# DeskClock1.net
KiCad netlist of a schematic drawn in Altium Designer
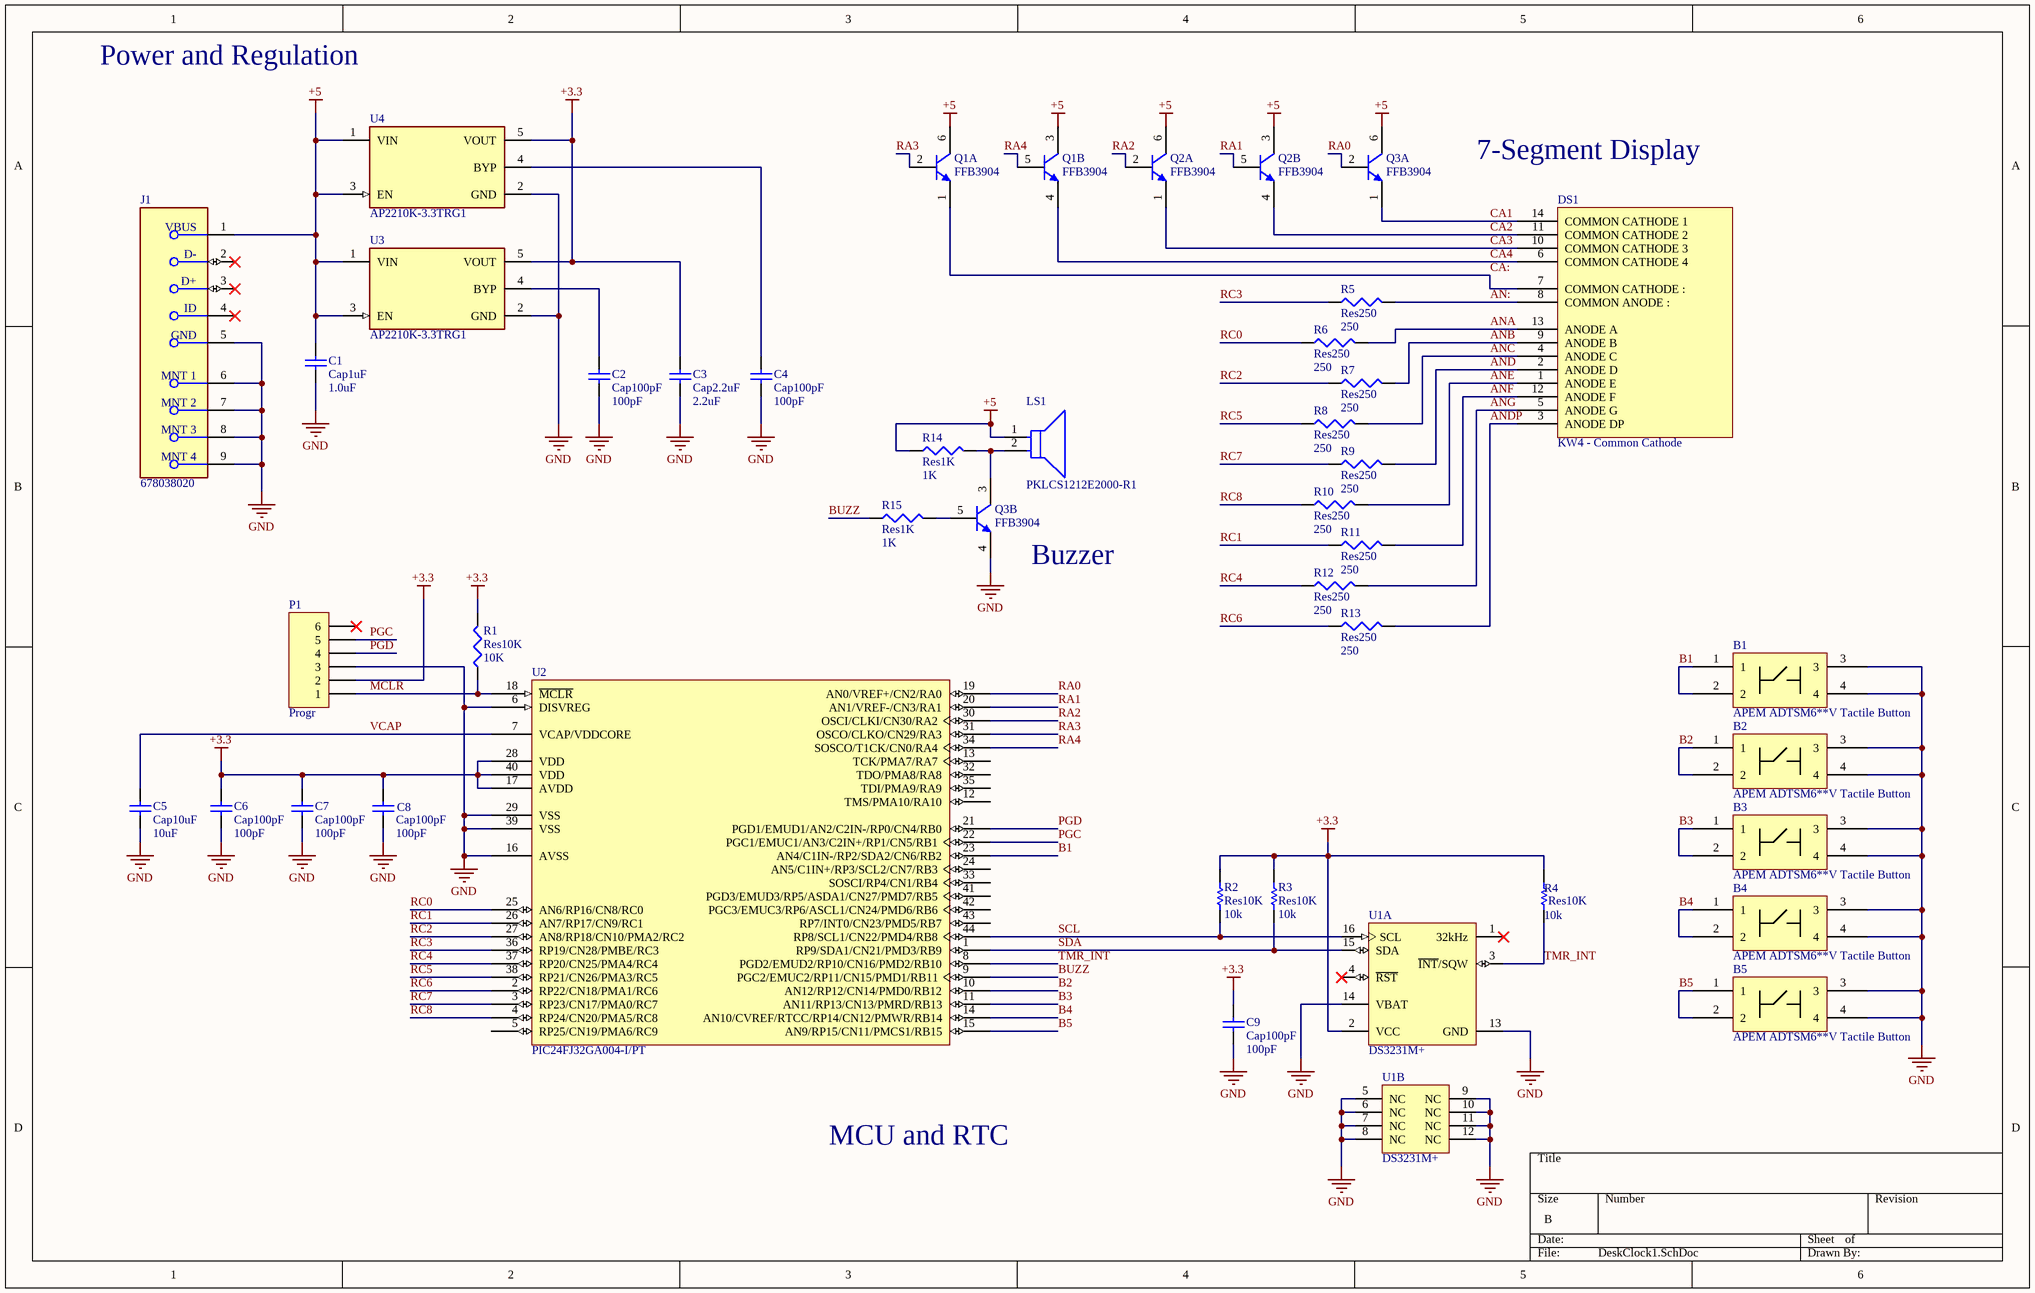
[diagram p0: DeskClock1.SchDoc]

(export (version "E")
  (design (tool "Eeschema 10.0.6"))
  (components
    (comp (ref "B1")
      (value "APEM ADTSM6**V Tactile Button")
      (footprint "ADTSM6**V")
      (description "ADTSM6**V")
      (libsource (lib "Button") (part "Button"))
    )
    (comp (ref "B2")
      (value "APEM ADTSM6**V Tactile Button")
      (footprint "ADTSM6**V")
      (description "ADTSM6**V")
      (libsource (lib "Button") (part "Button"))
    )
    (comp (ref "B3")
      (value "APEM ADTSM6**V Tactile Button")
      (footprint "ADTSM6**V")
      (description "ADTSM6**V")
      (libsource (lib "Button") (part "Button"))
    )
    (comp (ref "B4")
      (value "APEM ADTSM6**V Tactile Button")
      (footprint "ADTSM6**V")
      (description "ADTSM6**V")
      (libsource (lib "Button") (part "Button"))
    )
    (comp (ref "B5")
      (value "APEM ADTSM6**V Tactile Button")
      (footprint "ADTSM6**V")
      (description "ADTSM6**V")
      (libsource (lib "Button") (part "Button"))
    )
    (comp (ref "C1")
      (value "Cap1uF")
      (footprint "C1206")
      (description "Capacitor (Semiconductor SIM Model)")
      (fields (field (name "ALTIUM_VALUE") "1.0uF") (field (name "PUBLISHER") "Altium Limited"))
      (libsource (lib "Miscellaneous Devices") (part "Cap Semi"))
    )
    (comp (ref "C2")
      (value "Cap100pF")
      (footprint "C1206")
      (description "Capacitor (Semiconductor SIM Model)")
      (fields (field (name "ALTIUM_VALUE") "100pF") (field (name "PUBLISHER") "Altium Limited"))
      (libsource (lib "Miscellaneous Devices") (part "Cap Semi"))
    )
    (comp (ref "C3")
      (value "Cap2.2uF")
      (footprint "C1206")
      (description "Capacitor (Semiconductor SIM Model)")
      (fields (field (name "ALTIUM_VALUE") "2.2uF") (field (name "PUBLISHER") "Altium Limited"))
      (libsource (lib "Miscellaneous Devices") (part "Cap Semi"))
    )
    (comp (ref "C4")
      (value "Cap100pF")
      (footprint "C1206")
      (description "Capacitor (Semiconductor SIM Model)")
      (fields (field (name "ALTIUM_VALUE") "100pF") (field (name "PUBLISHER") "Altium Limited"))
      (libsource (lib "Miscellaneous Devices") (part "Cap Semi"))
    )
    (comp (ref "C5")
      (value "Cap10uF")
      (footprint "C1206")
      (description "Capacitor (Semiconductor SIM Model)")
      (fields (field (name "ALTIUM_VALUE") "10uF") (field (name "PUBLISHER") "Altium Limited"))
      (libsource (lib "Miscellaneous Devices") (part "Cap Semi"))
    )
    (comp (ref "C6")
      (value "Cap100pF")
      (footprint "C1206")
      (description "Capacitor (Semiconductor SIM Model)")
      (fields (field (name "ALTIUM_VALUE") "100pF") (field (name "PUBLISHER") "Altium Limited"))
      (libsource (lib "Miscellaneous Devices") (part "Cap Semi"))
    )
    (comp (ref "C7")
      (value "Cap100pF")
      (footprint "C1206")
      (description "Capacitor (Semiconductor SIM Model)")
      (fields (field (name "ALTIUM_VALUE") "100pF") (field (name "PUBLISHER") "Altium Limited"))
      (libsource (lib "Miscellaneous Devices") (part "Cap Semi"))
    )
    (comp (ref "C8")
      (value "Cap100pF")
      (footprint "C1206")
      (description "Capacitor (Semiconductor SIM Model)")
      (fields (field (name "ALTIUM_VALUE") "100pF") (field (name "PUBLISHER") "Altium Limited"))
      (libsource (lib "Miscellaneous Devices") (part "Cap Semi"))
    )
    (comp (ref "C9")
      (value "Cap100pF")
      (footprint "C1206")
      (description "Capacitor (Semiconductor SIM Model)")
      (fields (field (name "ALTIUM_VALUE") "100pF") (field (name "PUBLISHER") "Altium Limited"))
      (libsource (lib "Miscellaneous Devices") (part "Cap Semi"))
    )
    (comp (ref "DS1")
      (value "KW4 - Common Cathode")
      (footprint "KW4-56")
      (description "Lucky Light 4-digit 7 segment clock display")
      (libsource (lib "7SegDisplay") (part "KW4 - Common Cathode"))
    )
    (comp (ref "J1")
      (value "678038020")
      (footprint "FP-678038020-MFG")
      (description "CONN RCPT USB2.0 MINI AB SMD R/A")
      (fields
        (field (name "OCTOPART") "https://octopart.com/67803-8020-molex-7136109")
        (field (name "MANUFACTURER") "Molex")
      )
      (libsource (lib "Altium Content Vault") (part "4e344dc6d88d84069f7b4209354b9f9"))
    )
    (comp (ref "LS1")
      (value "PKLCS1212E2000-R1")
      (footprint "FP-PKLCS1212E2000-R1-MFG")
      (description "AUDIO PIEZO TRANSDUCER 12.5V SMD")
      (fields
        (field (name "MANUFACTURER") "Murata")
        (field (name "OCTOPART") "https://octopart.com/pklcs1212e2000-r1-murata-7123179")
      )
      (libsource (lib "Altium Content Vault") (part "5f581d31613f872430949aa526fd155"))
    )
    (comp (ref "P1")
      (value "Progr")
      (footprint "HDR1X6")
      (description "Header, 6-Pin")
      (fields (field (name "PUBLISHER") "Altium Limited"))
      (libsource (lib "Miscellaneous Connectors") (part "Header 6"))
    )
    (comp (ref "Q1")
      (value "FFB3904")
      (footprint "FAIR-SC70-6_V")
      (fields (field (name "MANUFACTURER") "FairchildSemiconductor"))
      (libsource (lib "Altium Content Vault") (part "BJT-NPN-EBC-EBC-6_A"))
    )
    (comp (ref "Q2")
      (value "FFB3904")
      (footprint "FAIR-SC70-6_V")
      (fields (field (name "MANUFACTURER") "FairchildSemiconductor"))
      (libsource (lib "Altium Content Vault") (part "BJT-NPN-EBC-EBC-6_A"))
    )
    (comp (ref "Q3")
      (value "FFB3904")
      (footprint "FAIR-SC70-6_V")
      (fields (field (name "MANUFACTURER") "FairchildSemiconductor"))
      (libsource (lib "Altium Content Vault") (part "BJT-NPN-EBC-EBC-6_A"))
    )
    (comp (ref "R1")
      (value "Res10K")
      (footprint "C1206")
      (description "Resistor")
      (fields (field (name "ALTIUM_VALUE") "10K") (field (name "PUBLISHER") "Altium Limited"))
      (libsource (lib "Miscellaneous Devices") (part "Res3"))
    )
    (comp (ref "R2")
      (value "Res10K")
      (footprint "C1206")
      (description "Resistor")
      (fields (field (name "ALTIUM_VALUE") "10k") (field (name "PUBLISHER") "Altium Limited"))
      (libsource (lib "Miscellaneous Devices") (part "Res1"))
    )
    (comp (ref "R3")
      (value "Res10K")
      (footprint "C1206")
      (description "Resistor")
      (fields (field (name "ALTIUM_VALUE") "10k") (field (name "PUBLISHER") "Altium Limited"))
      (libsource (lib "Miscellaneous Devices") (part "Res1"))
    )
    (comp (ref "R4")
      (value "Res10K")
      (footprint "C1206")
      (description "Resistor")
      (fields (field (name "ALTIUM_VALUE") "10k") (field (name "PUBLISHER") "Altium Limited"))
      (libsource (lib "Miscellaneous Devices") (part "Res1"))
    )
    (comp (ref "R5")
      (value "Res250")
      (footprint "C1206")
      (description "Resistor")
      (fields (field (name "ALTIUM_VALUE") "250") (field (name "PUBLISHER") "Altium Limited"))
      (libsource (lib "Miscellaneous Devices") (part "Res3"))
    )
    (comp (ref "R6")
      (value "Res250")
      (footprint "C1206")
      (description "Resistor")
      (fields (field (name "ALTIUM_VALUE") "250") (field (name "PUBLISHER") "Altium Limited"))
      (libsource (lib "Miscellaneous Devices") (part "Res3"))
    )
    (comp (ref "R7")
      (value "Res250")
      (footprint "C1206")
      (description "Resistor")
      (fields (field (name "ALTIUM_VALUE") "250") (field (name "PUBLISHER") "Altium Limited"))
      (libsource (lib "Miscellaneous Devices") (part "Res3"))
    )
    (comp (ref "R8")
      (value "Res250")
      (footprint "C1206")
      (description "Resistor")
      (fields (field (name "ALTIUM_VALUE") "250") (field (name "PUBLISHER") "Altium Limited"))
      (libsource (lib "Miscellaneous Devices") (part "Res3"))
    )
    (comp (ref "R9")
      (value "Res250")
      (footprint "C1206")
      (description "Resistor")
      (fields (field (name "ALTIUM_VALUE") "250") (field (name "PUBLISHER") "Altium Limited"))
      (libsource (lib "Miscellaneous Devices") (part "Res3"))
    )
    (comp (ref "R10")
      (value "Res250")
      (footprint "C1206")
      (description "Resistor")
      (fields (field (name "ALTIUM_VALUE") "250") (field (name "PUBLISHER") "Altium Limited"))
      (libsource (lib "Miscellaneous Devices") (part "Res3"))
    )
    (comp (ref "R11")
      (value "Res250")
      (footprint "C1206")
      (description "Resistor")
      (fields (field (name "ALTIUM_VALUE") "250") (field (name "PUBLISHER") "Altium Limited"))
      (libsource (lib "Miscellaneous Devices") (part "Res3"))
    )
    (comp (ref "R12")
      (value "Res250")
      (footprint "C1206")
      (description "Resistor")
      (fields (field (name "ALTIUM_VALUE") "250") (field (name "PUBLISHER") "Altium Limited"))
      (libsource (lib "Miscellaneous Devices") (part "Res3"))
    )
    (comp (ref "R13")
      (value "Res250")
      (footprint "C1206")
      (description "Resistor")
      (fields (field (name "ALTIUM_VALUE") "250") (field (name "PUBLISHER") "Altium Limited"))
      (libsource (lib "Miscellaneous Devices") (part "Res3"))
    )
    (comp (ref "R14")
      (value "Res1K")
      (footprint "C1206")
      (description "Resistor")
      (fields (field (name "ALTIUM_VALUE") "1K") (field (name "PUBLISHER") "Altium Limited"))
      (libsource (lib "Miscellaneous Devices") (part "Res3"))
    )
    (comp (ref "R15")
      (value "Res1K")
      (footprint "C1206")
      (description "Resistor")
      (fields (field (name "ALTIUM_VALUE") "1K") (field (name "PUBLISHER") "Altium Limited"))
      (libsource (lib "Miscellaneous Devices") (part "Res3"))
    )
    (comp (ref "U1")
      (value "DS3231M+")
      (footprint "W16MK+1_M")
      (description "+/-5ppm, MEMS based Real-Time Clock, I2C Interface, 16-Pin SO, -40 to 85 degC, Pb-Free")
      (libsource (lib "Altium Content Vault") (part "PR-RTC-DS3231M-IL16"))
    )
    (comp (ref "U2")
      (value "PIC24FJ32GA004-I/PT")
      (footprint "TQFP-PT44_L")
      (libsource (lib "Altium Content Vault") (part "MC-16B-16GA004-TQFP44"))
    )
    (comp (ref "U3")
      (value "AP2210K-3.3TRG1")
      (footprint "FP-SOT25-MFG")
      (description "IC REG LINEAR 3.3V 300MA SOT23-5")
      (fields
        (field (name "MANUFACTURER") "Diodes")
        (field (name "OCTOPART") "https://octopart.com/ap2210k-3.3trg1-diodes+inc.-30954630")
      )
      (libsource (lib "Altium Content Vault") (part "c51eb117839baecd597f0ee1e447120"))
    )
    (comp (ref "U4")
      (value "AP2210K-3.3TRG1")
      (footprint "FP-SOT25-MFG")
      (description "IC REG LINEAR 3.3V 300MA SOT23-5")
      (fields
        (field (name "MANUFACTURER") "Diodes")
        (field (name "OCTOPART") "https://octopart.com/ap2210k-3.3trg1-diodes+inc.-30954630")
      )
      (libsource (lib "Altium Content Vault") (part "c51eb117839baecd597f0ee1e447120"))
    )
  )
  (nets
    (net (code "1") (name "+3.3") (class "Default")
      (node (ref "C3") (pin "2") (pinfunction "2_2") (pintype "passive"))
      (node (ref "C6") (pin "2") (pinfunction "2_2") (pintype "passive"))
      (node (ref "C7") (pin "2") (pinfunction "2_2") (pintype "passive"))
      (node (ref "C8") (pin "2") (pinfunction "2_2") (pintype "passive"))
      (node (ref "C9") (pin "2") (pinfunction "2_2") (pintype "passive"))
      (node (ref "P1") (pin "2") (pinfunction "2_2") (pintype "passive"))
      (node (ref "R1") (pin "2") (pinfunction "2_2") (pintype "passive"))
      (node (ref "R2") (pin "2") (pinfunction "2_2") (pintype "passive"))
      (node (ref "R3") (pin "2") (pinfunction "2_2") (pintype "passive"))
      (node (ref "R4") (pin "2") (pinfunction "2_2") (pintype "passive"))
      (node (ref "U1") (pin "2") (pinfunction "VCC_2") (pintype "power_in"))
      (node (ref "U2") (pin "17") (pinfunction "AVDD_17") (pintype "power_in"))
      (node (ref "U2") (pin "28") (pinfunction "VDD_28") (pintype "power_in"))
      (node (ref "U2") (pin "40") (pinfunction "VDD_40") (pintype "power_in"))
      (node (ref "U3") (pin "5") (pinfunction "VOUT_5") (pintype "power_in"))
      (node (ref "U4") (pin "5") (pinfunction "VOUT_5") (pintype "power_in"))
    )
    (net (code "2") (name "+5") (class "Default")
      (node (ref "C1") (pin "2") (pinfunction "2_2") (pintype "passive"))
      (node (ref "J1") (pin "1") (pinfunction "VBUS_1") (pintype "power_in"))
      (node (ref "LS1") (pin "1") (pinfunction "1_1") (pintype "passive"))
      (node (ref "Q1") (pin "3") (pinfunction "C2_3") (pintype "passive"))
      (node (ref "Q1") (pin "6") (pinfunction "C1_6") (pintype "passive"))
      (node (ref "Q2") (pin "3") (pinfunction "C2_3") (pintype "passive"))
      (node (ref "Q2") (pin "6") (pinfunction "C1_6") (pintype "passive"))
      (node (ref "Q3") (pin "6") (pinfunction "C1_6") (pintype "passive"))
      (node (ref "R14") (pin "1") (pinfunction "1_1") (pintype "passive"))
      (node (ref "U3") (pin "1") (pinfunction "VIN_1") (pintype "power_in"))
      (node (ref "U3") (pin "3") (pinfunction "EN_3") (pintype "input"))
      (node (ref "U4") (pin "1") (pinfunction "VIN_1") (pintype "power_in"))
      (node (ref "U4") (pin "3") (pinfunction "EN_3") (pintype "input"))
    )
    (net (code "3") (name "/AN:") (class "Default")
      (node (ref "DS1") (pin "8") (pinfunction "COMMON_ANODE_:_8") (pintype "passive"))
      (node (ref "R5") (pin "2") (pinfunction "2_2") (pintype "passive"))
    )
    (net (code "4") (name "/ANA") (class "Default")
      (node (ref "DS1") (pin "13") (pinfunction "ANODE_A_13") (pintype "passive"))
      (node (ref "R6") (pin "2") (pinfunction "2_2") (pintype "passive"))
    )
    (net (code "5") (name "/ANB") (class "Default")
      (node (ref "DS1") (pin "9") (pinfunction "ANODE_B_9") (pintype "passive"))
      (node (ref "R7") (pin "2") (pinfunction "2_2") (pintype "passive"))
    )
    (net (code "6") (name "/ANC") (class "Default")
      (node (ref "DS1") (pin "4") (pinfunction "ANODE_C_4") (pintype "passive"))
      (node (ref "R8") (pin "2") (pinfunction "2_2") (pintype "passive"))
    )
    (net (code "7") (name "/AND") (class "Default")
      (node (ref "DS1") (pin "2") (pinfunction "ANODE_D_2") (pintype "passive"))
      (node (ref "R9") (pin "2") (pinfunction "2_2") (pintype "passive"))
    )
    (net (code "8") (name "/ANDP") (class "Default")
      (node (ref "DS1") (pin "3") (pinfunction "ANODE_DP_3") (pintype "passive"))
      (node (ref "R13") (pin "2") (pinfunction "2_2") (pintype "passive"))
    )
    (net (code "9") (name "/ANE") (class "Default")
      (node (ref "DS1") (pin "1") (pinfunction "ANODE_E_1") (pintype "passive"))
      (node (ref "R10") (pin "2") (pinfunction "2_2") (pintype "passive"))
    )
    (net (code "10") (name "/ANF") (class "Default")
      (node (ref "DS1") (pin "12") (pinfunction "ANODE_F_12") (pintype "passive"))
      (node (ref "R11") (pin "2") (pinfunction "2_2") (pintype "passive"))
    )
    (net (code "11") (name "/ANG") (class "Default")
      (node (ref "DS1") (pin "5") (pinfunction "ANODE_G_5") (pintype "passive"))
      (node (ref "R12") (pin "2") (pinfunction "2_2") (pintype "passive"))
    )
    (net (code "12") (name "/B1") (class "Default")
      (node (ref "B1") (pin "1") (pinfunction "1_1") (pintype "passive"))
      (node (ref "B1") (pin "2") (pinfunction "2_2") (pintype "passive"))
      (node (ref "U2") (pin "23") (pinfunction "AN4/C1IN-/RP2/SDA2/CN6/RB2_23") (pintype "bidirectional"))
    )
    (net (code "13") (name "/B2") (class "Default")
      (node (ref "B2") (pin "1") (pinfunction "1_1") (pintype "passive"))
      (node (ref "B2") (pin "2") (pinfunction "2_2") (pintype "passive"))
      (node (ref "U2") (pin "10") (pinfunction "AN12/RP12/CN14/PMD0/RB12_10") (pintype "bidirectional"))
    )
    (net (code "14") (name "/B3") (class "Default")
      (node (ref "B3") (pin "1") (pinfunction "1_1") (pintype "passive"))
      (node (ref "B3") (pin "2") (pinfunction "2_2") (pintype "passive"))
      (node (ref "U2") (pin "11") (pinfunction "AN11/RP13/CN13/PMRD/RB13_11") (pintype "bidirectional"))
    )
    (net (code "15") (name "/B4") (class "Default")
      (node (ref "B4") (pin "1") (pinfunction "1_1") (pintype "passive"))
      (node (ref "B4") (pin "2") (pinfunction "2_2") (pintype "passive"))
      (node (ref "U2") (pin "14") (pinfunction "AN10/CVREF/RTCC/RP14/CN12/PMWR/RB14_14") (pintype "bidirectional"))
    )
    (net (code "16") (name "/B5") (class "Default")
      (node (ref "B5") (pin "1") (pinfunction "1_1") (pintype "passive"))
      (node (ref "B5") (pin "2") (pinfunction "2_2") (pintype "passive"))
      (node (ref "U2") (pin "15") (pinfunction "AN9/RP15/CN11/PMCS1/RB15_15") (pintype "bidirectional"))
    )
    (net (code "17") (name "/BUZZ") (class "Default")
      (node (ref "R15") (pin "1") (pinfunction "1_1") (pintype "passive"))
      (node (ref "U2") (pin "9") (pinfunction "PGC2/EMUC2/RP11/CN15/PMD1/RB11_9") (pintype "bidirectional"))
    )
    (net (code "18") (name "/CA1") (class "Default")
      (node (ref "DS1") (pin "14") (pinfunction "COMMON_CATHODE_1_14") (pintype "passive"))
      (node (ref "Q3") (pin "1") (pinfunction "E1_1") (pintype "passive"))
    )
    (net (code "19") (name "/CA2") (class "Default")
      (node (ref "DS1") (pin "11") (pinfunction "COMMON_CATHODE_2_11") (pintype "passive"))
      (node (ref "Q2") (pin "4") (pinfunction "E2_4") (pintype "passive"))
    )
    (net (code "20") (name "/CA3") (class "Default")
      (node (ref "DS1") (pin "10") (pinfunction "COMMON_CATHODE_3_10") (pintype "passive"))
      (node (ref "Q2") (pin "1") (pinfunction "E1_1") (pintype "passive"))
    )
    (net (code "21") (name "/CA4") (class "Default")
      (node (ref "DS1") (pin "6") (pinfunction "COMMON_CATHODE_4_6") (pintype "passive"))
      (node (ref "Q1") (pin "4") (pinfunction "E2_4") (pintype "passive"))
    )
    (net (code "22") (name "/CA:") (class "Default")
      (node (ref "DS1") (pin "7") (pinfunction "COMMON_CATHODE_:_7") (pintype "passive"))
      (node (ref "Q1") (pin "1") (pinfunction "E1_1") (pintype "passive"))
    )
    (net (code "23") (name "/MCLR") (class "Default")
      (node (ref "P1") (pin "1") (pinfunction "1_1") (pintype "passive"))
      (node (ref "R1") (pin "1") (pinfunction "1_1") (pintype "passive"))
      (node (ref "U2") (pin "18") (pinfunction "~{MCLR}_18") (pintype "input"))
    )
    (net (code "24") (name "/PGC") (class "Default")
      (node (ref "P1") (pin "5") (pinfunction "5_5") (pintype "passive"))
      (node (ref "U2") (pin "22") (pinfunction "PGC1/EMUC1/AN3/C2IN+/RP1/CN5/RB1_22") (pintype "bidirectional"))
    )
    (net (code "25") (name "/PGD") (class "Default")
      (node (ref "P1") (pin "4") (pinfunction "4_4") (pintype "passive"))
      (node (ref "U2") (pin "21") (pinfunction "PGD1/EMUD1/AN2/C2IN-/RP0/CN4/RB0_21") (pintype "bidirectional"))
    )
    (net (code "26") (name "/RA0") (class "Default")
      (node (ref "Q3") (pin "2") (pinfunction "B1_2") (pintype "passive"))
      (node (ref "U2") (pin "19") (pinfunction "AN0/VREF+/CN2/RA0_19") (pintype "bidirectional"))
    )
    (net (code "27") (name "/RA1") (class "Default")
      (node (ref "Q2") (pin "5") (pinfunction "B2_5") (pintype "passive"))
      (node (ref "U2") (pin "20") (pinfunction "AN1/VREF-/CN3/RA1_20") (pintype "bidirectional"))
    )
    (net (code "28") (name "/RA2") (class "Default")
      (node (ref "Q2") (pin "2") (pinfunction "B1_2") (pintype "passive"))
      (node (ref "U2") (pin "30") (pinfunction "OSCI/CLKI/CN30/RA2_30") (pintype "bidirectional"))
    )
    (net (code "29") (name "/RA3") (class "Default")
      (node (ref "Q1") (pin "2") (pinfunction "B1_2") (pintype "passive"))
      (node (ref "U2") (pin "31") (pinfunction "OSCO/CLKO/CN29/RA3_31") (pintype "bidirectional"))
    )
    (net (code "30") (name "/RA4") (class "Default")
      (node (ref "Q1") (pin "5") (pinfunction "B2_5") (pintype "passive"))
      (node (ref "U2") (pin "34") (pinfunction "SOSCO/T1CK/CN0/RA4_34") (pintype "bidirectional"))
    )
    (net (code "31") (name "/RC0") (class "Default")
      (node (ref "R6") (pin "1") (pinfunction "1_1") (pintype "passive"))
      (node (ref "U2") (pin "25") (pinfunction "AN6/RP16/CN8/RC0_25") (pintype "bidirectional"))
    )
    (net (code "32") (name "/RC1") (class "Default")
      (node (ref "R11") (pin "1") (pinfunction "1_1") (pintype "passive"))
      (node (ref "U2") (pin "26") (pinfunction "AN7/RP17/CN9/RC1_26") (pintype "bidirectional"))
    )
    (net (code "33") (name "/RC2") (class "Default")
      (node (ref "R7") (pin "1") (pinfunction "1_1") (pintype "passive"))
      (node (ref "U2") (pin "27") (pinfunction "AN8/RP18/CN10/PMA2/RC2_27") (pintype "bidirectional"))
    )
    (net (code "34") (name "/RC3") (class "Default")
      (node (ref "R5") (pin "1") (pinfunction "1_1") (pintype "passive"))
      (node (ref "U2") (pin "36") (pinfunction "RP19/CN28/PMBE/RC3_36") (pintype "bidirectional"))
    )
    (net (code "35") (name "/RC4") (class "Default")
      (node (ref "R12") (pin "1") (pinfunction "1_1") (pintype "passive"))
      (node (ref "U2") (pin "37") (pinfunction "RP20/CN25/PMA4/RC4_37") (pintype "bidirectional"))
    )
    (net (code "36") (name "/RC5") (class "Default")
      (node (ref "R8") (pin "1") (pinfunction "1_1") (pintype "passive"))
      (node (ref "U2") (pin "38") (pinfunction "RP21/CN26/PMA3/RC5_38") (pintype "bidirectional"))
    )
    (net (code "37") (name "/RC6") (class "Default")
      (node (ref "R13") (pin "1") (pinfunction "1_1") (pintype "passive"))
      (node (ref "U2") (pin "2") (pinfunction "RP22/CN18/PMA1/RC6_2") (pintype "bidirectional"))
    )
    (net (code "38") (name "/RC7") (class "Default")
      (node (ref "R9") (pin "1") (pinfunction "1_1") (pintype "passive"))
      (node (ref "U2") (pin "3") (pinfunction "RP23/CN17/PMA0/RC7_3") (pintype "bidirectional"))
    )
    (net (code "39") (name "/RC8") (class "Default")
      (node (ref "R10") (pin "1") (pinfunction "1_1") (pintype "passive"))
      (node (ref "U2") (pin "4") (pinfunction "RP24/CN20/PMA5/RC8_4") (pintype "bidirectional"))
    )
    (net (code "40") (name "/SCL") (class "Default")
      (node (ref "R2") (pin "1") (pinfunction "1_1") (pintype "passive"))
      (node (ref "U1") (pin "16") (pinfunction "SCL_16") (pintype "input"))
      (node (ref "U2") (pin "44") (pinfunction "RP8/SCL1/CN22/PMD4/RB8_44") (pintype "bidirectional"))
    )
    (net (code "41") (name "/SDA") (class "Default")
      (node (ref "R3") (pin "1") (pinfunction "1_1") (pintype "passive"))
      (node (ref "U1") (pin "15") (pinfunction "SDA_15") (pintype "bidirectional"))
      (node (ref "U2") (pin "1") (pinfunction "RP9/SDA1/CN21/PMD3/RB9_1") (pintype "bidirectional"))
    )
    (net (code "42") (name "/TMR_INT") (class "Default")
      (node (ref "R4") (pin "1") (pinfunction "1_1") (pintype "passive"))
      (node (ref "U1") (pin "3") (pinfunction "~{INT}/SQW_3") (pintype "bidirectional"))
      (node (ref "U2") (pin "8") (pinfunction "PGD2/EMUD2/RP10/CN16/PMD2/RB10_8") (pintype "bidirectional"))
    )
    (net (code "43") (name "/VCAP") (class "Default")
      (node (ref "C5") (pin "2") (pinfunction "2_2") (pintype "passive"))
      (node (ref "U2") (pin "7") (pinfunction "VCAP/VDDCORE_7") (pintype "power_in"))
    )
    (net (code "44") (name "GND") (class "Default")
      (node (ref "B1") (pin "3") (pinfunction "3_3") (pintype "passive"))
      (node (ref "B1") (pin "4") (pinfunction "4_4") (pintype "passive"))
      (node (ref "B2") (pin "3") (pinfunction "3_3") (pintype "passive"))
      (node (ref "B2") (pin "4") (pinfunction "4_4") (pintype "passive"))
      (node (ref "B3") (pin "3") (pinfunction "3_3") (pintype "passive"))
      (node (ref "B3") (pin "4") (pinfunction "4_4") (pintype "passive"))
      (node (ref "B4") (pin "3") (pinfunction "3_3") (pintype "passive"))
      (node (ref "B4") (pin "4") (pinfunction "4_4") (pintype "passive"))
      (node (ref "B5") (pin "3") (pinfunction "3_3") (pintype "passive"))
      (node (ref "B5") (pin "4") (pinfunction "4_4") (pintype "passive"))
      (node (ref "C1") (pin "1") (pinfunction "1_1") (pintype "passive"))
      (node (ref "C2") (pin "1") (pinfunction "1_1") (pintype "passive"))
      (node (ref "C3") (pin "1") (pinfunction "1_1") (pintype "passive"))
      (node (ref "C4") (pin "1") (pinfunction "1_1") (pintype "passive"))
      (node (ref "C5") (pin "1") (pinfunction "1_1") (pintype "passive"))
      (node (ref "C6") (pin "1") (pinfunction "1_1") (pintype "passive"))
      (node (ref "C7") (pin "1") (pinfunction "1_1") (pintype "passive"))
      (node (ref "C8") (pin "1") (pinfunction "1_1") (pintype "passive"))
      (node (ref "C9") (pin "1") (pinfunction "1_1") (pintype "passive"))
      (node (ref "J1") (pin "5") (pinfunction "GND_5") (pintype "power_in"))
      (node (ref "J1") (pin "6") (pinfunction "MNT_1_6") (pintype "passive"))
      (node (ref "J1") (pin "7") (pinfunction "MNT_2_7") (pintype "passive"))
      (node (ref "J1") (pin "8") (pinfunction "MNT_3_8") (pintype "passive"))
      (node (ref "J1") (pin "9") (pinfunction "MNT_4_9") (pintype "passive"))
      (node (ref "P1") (pin "3") (pinfunction "3_3") (pintype "passive"))
      (node (ref "Q3") (pin "4") (pinfunction "E2_4") (pintype "passive"))
      (node (ref "U1") (pin "10") (pinfunction "NC_10") (pintype "passive"))
      (node (ref "U1") (pin "11") (pinfunction "NC_11") (pintype "passive"))
      (node (ref "U1") (pin "12") (pinfunction "NC_12") (pintype "passive"))
      (node (ref "U1") (pin "13") (pinfunction "GND_13") (pintype "power_in"))
      (node (ref "U1") (pin "14") (pinfunction "VBAT_14") (pintype "power_in"))
      (node (ref "U1") (pin "5") (pinfunction "NC_5") (pintype "passive"))
      (node (ref "U1") (pin "6") (pinfunction "NC_6") (pintype "passive"))
      (node (ref "U1") (pin "7") (pinfunction "NC_7") (pintype "passive"))
      (node (ref "U1") (pin "8") (pinfunction "NC_8") (pintype "passive"))
      (node (ref "U1") (pin "9") (pinfunction "NC_9") (pintype "passive"))
      (node (ref "U2") (pin "16") (pinfunction "AVSS_16") (pintype "power_in"))
      (node (ref "U2") (pin "29") (pinfunction "VSS_29") (pintype "power_in"))
      (node (ref "U2") (pin "39") (pinfunction "VSS_39") (pintype "power_in"))
      (node (ref "U2") (pin "6") (pinfunction "DISVREG_6") (pintype "input"))
      (node (ref "U3") (pin "2") (pinfunction "GND_2") (pintype "power_in"))
      (node (ref "U4") (pin "2") (pinfunction "GND_2") (pintype "power_in"))
    )
    (net (code "45") (name "Net-(Q3B-B2)") (class "Default")
      (node (ref "Q3") (pin "5") (pinfunction "B2_5") (pintype "passive"))
      (node (ref "R15") (pin "2") (pinfunction "2_2") (pintype "passive"))
    )
    (net (code "46") (name "Net-(Q3B-C2)") (class "Default")
      (node (ref "LS1") (pin "2") (pinfunction "2_2") (pintype "passive"))
      (node (ref "Q3") (pin "3") (pinfunction "C2_3") (pintype "passive"))
      (node (ref "R14") (pin "2") (pinfunction "2_2") (pintype "passive"))
    )
    (net (code "47") (name "Net-(U3-BYP)") (class "Default")
      (node (ref "C2") (pin "2") (pinfunction "2_2") (pintype "passive"))
      (node (ref "U3") (pin "4") (pinfunction "BYP_4") (pintype "passive"))
    )
    (net (code "48") (name "Net-(U4-BYP)") (class "Default")
      (node (ref "C4") (pin "2") (pinfunction "2_2") (pintype "passive"))
      (node (ref "U4") (pin "4") (pinfunction "BYP_4") (pintype "passive"))
    )
    (net (code "49") (name "unconnected-(J1-D+-Pad3)") (class "Default")
      (node (ref "J1") (pin "3") (pinfunction "D+_3") (pintype "bidirectional+no_connect"))
    )
    (net (code "50") (name "unconnected-(J1-D--Pad2)") (class "Default")
      (node (ref "J1") (pin "2") (pinfunction "D-_2") (pintype "bidirectional+no_connect"))
    )
    (net (code "51") (name "unconnected-(J1-ID-Pad4)") (class "Default")
      (node (ref "J1") (pin "4") (pinfunction "ID_4") (pintype "passive+no_connect"))
    )
    (net (code "52") (name "unconnected-(P1-Pad6)") (class "Default")
      (node (ref "P1") (pin "6") (pinfunction "6_6") (pintype "passive+no_connect"))
    )
    (net (code "53") (name "unconnected-(U1A-32kHz-Pad1)") (class "Default")
      (node (ref "U1") (pin "1") (pinfunction "32kHz_1") (pintype "open_collector+no_connect"))
    )
    (net (code "54") (name "unconnected-(U1A-~{RST}-Pad4)") (class "Default")
      (node (ref "U1") (pin "4") (pinfunction "~{RST}_4") (pintype "bidirectional+no_connect"))
    )
    (net (code "55") (name "unconnected-(U2-AN5{slash}C1IN+{slash}RP3{slash}SCL2{slash}CN7{slash}RB3-Pad24)") (class "Default")
      (node (ref "U2") (pin "24") (pinfunction "AN5/C1IN+/RP3/SCL2/CN7/RB3_24") (pintype "bidirectional"))
    )
    (net (code "56") (name "unconnected-(U2-PGC3{slash}EMUC3{slash}RP6{slash}ASCL1{slash}CN24{slash}PMD6{slash}RB6-Pad42)") (class "Default")
      (node (ref "U2") (pin "42") (pinfunction "PGC3/EMUC3/RP6/ASCL1/CN24/PMD6/RB6_42") (pintype "bidirectional"))
    )
    (net (code "57") (name "unconnected-(U2-PGD3{slash}EMUD3{slash}RP5{slash}ASDA1{slash}CN27{slash}PMD7{slash}RB5-Pad41)") (class "Default")
      (node (ref "U2") (pin "41") (pinfunction "PGD3/EMUD3/RP5/ASDA1/CN27/PMD7/RB5_41") (pintype "bidirectional"))
    )
    (net (code "58") (name "unconnected-(U2-RP7{slash}INT0{slash}CN23{slash}PMD5{slash}RB7-Pad43)") (class "Default")
      (node (ref "U2") (pin "43") (pinfunction "RP7/INT0/CN23/PMD5/RB7_43") (pintype "bidirectional"))
    )
    (net (code "59") (name "unconnected-(U2-RP25{slash}CN19{slash}PMA6{slash}RC9-Pad5)") (class "Default")
      (node (ref "U2") (pin "5") (pinfunction "RP25/CN19/PMA6/RC9_5") (pintype "bidirectional"))
    )
    (net (code "60") (name "unconnected-(U2-SOSCI{slash}RP4{slash}CN1{slash}RB4-Pad33)") (class "Default")
      (node (ref "U2") (pin "33") (pinfunction "SOSCI/RP4/CN1/RB4_33") (pintype "bidirectional"))
    )
    (net (code "61") (name "unconnected-(U2-TCK{slash}PMA7{slash}RA7-Pad13)") (class "Default")
      (node (ref "U2") (pin "13") (pinfunction "TCK/PMA7/RA7_13") (pintype "bidirectional"))
    )
    (net (code "62") (name "unconnected-(U2-TDI{slash}PMA9{slash}RA9-Pad35)") (class "Default")
      (node (ref "U2") (pin "35") (pinfunction "TDI/PMA9/RA9_35") (pintype "bidirectional"))
    )
    (net (code "63") (name "unconnected-(U2-TDO{slash}PMA8{slash}RA8-Pad32)") (class "Default")
      (node (ref "U2") (pin "32") (pinfunction "TDO/PMA8/RA8_32") (pintype "bidirectional"))
    )
    (net (code "64") (name "unconnected-(U2-TMS{slash}PMA10{slash}RA10-Pad12)") (class "Default")
      (node (ref "U2") (pin "12") (pinfunction "TMS/PMA10/RA10_12") (pintype "bidirectional"))
    )
  )
)
